# Tiny-RC-Serial.net
KiCad netlist of a schematic drawn in EAGLE
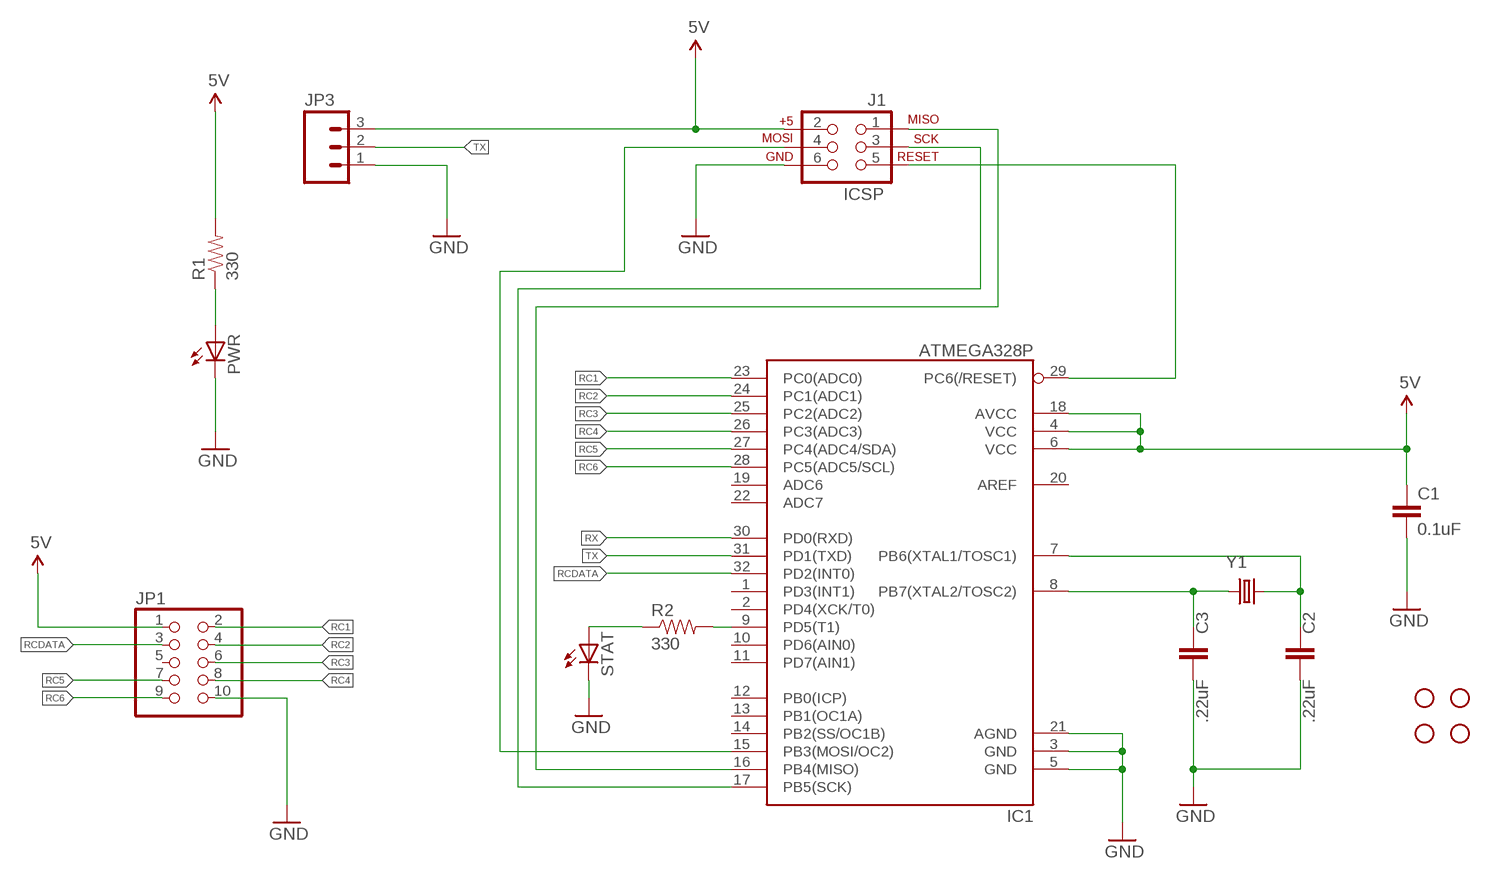
[diagram p0: schematic, sheet 1]

(export (version "E")
  (design (tool "Eeschema 10.0.6"))
  (components
    (comp (ref "C1")
      (value "0.1uF")
      (footprint "eagle-import:CAP-PTH-SMALL-KIT")
      (libsource (lib "eagle-import") (part "CAPKIT"))
    )
    (comp (ref "C2")
      (value ".22uF")
      (footprint "eagle-import:CAP-PTH-SMALL-KIT")
      (libsource (lib "eagle-import") (part "CAPKIT"))
    )
    (comp (ref "C3")
      (value ".22uF")
      (footprint "eagle-import:CAP-PTH-SMALL-KIT")
      (libsource (lib "eagle-import") (part "CAPKIT"))
    )
    (comp (ref "IC1")
      (value "ATMEGA328P")
      (footprint "eagle-import:TQFP32-08")
      (libsource (lib "eagle-import") (part "ATMEGA328_SMT"))
    )
    (comp (ref "J1")
      (value "ICSP")
      (footprint "eagle-import:2X3")
      (libsource (lib "eagle-import") (part "AVR_SPI_PRG_6PTH"))
    )
    (comp (ref "JP1")
      (value "PINHD-2X5")
      (footprint "eagle-import:2X05")
      (libsource (lib "eagle-import") (part "PINHD-2X5"))
    )
    (comp (ref "JP3")
      (value "M03PTH")
      (footprint "eagle-import:1X03")
      (libsource (lib "eagle-import") (part "M03PTH"))
    )
    (comp (ref "PWR")
      (value "LED1206")
      (footprint "eagle-import:LED-1206")
      (libsource (lib "eagle-import") (part "LED1206"))
    )
    (comp (ref "R1")
      (value "330")
      (footprint "eagle-import:1206")
      (libsource (lib "eagle-import") (part "RESISTOR1206"))
    )
    (comp (ref "R2")
      (value "330")
      (footprint "eagle-import:1206")
      (libsource (lib "eagle-import") (part "RESISTOR1206"))
    )
    (comp (ref "S1")
      (value "STAND-OFFTIGHT")
      (footprint "eagle-import:STAND-OFF-TIGHT")
      (libsource (lib "eagle-import") (part "STAND-OFFTIGHT"))
    )
    (comp (ref "S2")
      (value "STAND-OFFTIGHT")
      (footprint "eagle-import:STAND-OFF-TIGHT")
      (libsource (lib "eagle-import") (part "STAND-OFFTIGHT"))
    )
    (comp (ref "S3")
      (value "STAND-OFFTIGHT")
      (footprint "eagle-import:STAND-OFF-TIGHT")
      (libsource (lib "eagle-import") (part "STAND-OFFTIGHT"))
    )
    (comp (ref "S4")
      (value "STAND-OFFTIGHT")
      (footprint "eagle-import:STAND-OFF-TIGHT")
      (libsource (lib "eagle-import") (part "STAND-OFFTIGHT"))
    )
    (comp (ref "STAT")
      (value "LED1206")
      (footprint "eagle-import:LED-1206")
      (libsource (lib "eagle-import") (part "LED1206"))
    )
    (comp (ref "Y1")
      (value "20Mhz")
      (footprint "eagle-import:HC49US")
      (libsource (lib "eagle-import") (part "CRYSTALHC49US"))
    )
  )
  (nets
    (net (code "1") (name "5V") (class "Default")
      (node (ref "C1") (pin "1") (pinfunction "1_1") (pintype "passive"))
      (node (ref "IC1") (pin "18") (pinfunction "AVCC_18") (pintype "bidirectional"))
      (node (ref "IC1") (pin "4") (pinfunction "VCC_4") (pintype "bidirectional"))
      (node (ref "IC1") (pin "6") (pinfunction "VCC_6") (pintype "bidirectional"))
      (node (ref "J1") (pin "2") (pinfunction "2_2") (pintype "passive"))
      (node (ref "JP1") (pin "1") (pinfunction "1_1") (pintype "passive"))
      (node (ref "JP3") (pin "3") (pinfunction "3_3") (pintype "passive"))
      (node (ref "R1") (pin "2") (pinfunction "2_2") (pintype "passive"))
    )
    (net (code "2") (name "GND") (class "Default")
      (node (ref "C1") (pin "2") (pinfunction "2_2") (pintype "passive"))
      (node (ref "C2") (pin "2") (pinfunction "2_2") (pintype "passive"))
      (node (ref "C3") (pin "2") (pinfunction "2_2") (pintype "passive"))
      (node (ref "IC1") (pin "21") (pinfunction "AGND_21") (pintype "bidirectional"))
      (node (ref "IC1") (pin "3") (pinfunction "GND_3") (pintype "bidirectional"))
      (node (ref "IC1") (pin "5") (pinfunction "GND_5") (pintype "bidirectional"))
      (node (ref "J1") (pin "6") (pinfunction "6_6") (pintype "passive"))
      (node (ref "JP1") (pin "10") (pinfunction "10_10") (pintype "passive"))
      (node (ref "JP3") (pin "1") (pinfunction "1_1") (pintype "passive"))
      (node (ref "PWR") (pin "C") (pinfunction "C_C") (pintype "passive"))
      (node (ref "STAT") (pin "C") (pinfunction "C_C") (pintype "passive"))
    )
    (net (code "3") (name "Net-(IC1-PB3(MOSI{slash}OC2))") (class "Default")
      (node (ref "IC1") (pin "15") (pinfunction "PB3(MOSI/OC2)_15") (pintype "bidirectional"))
      (node (ref "J1") (pin "4") (pinfunction "4_4") (pintype "passive"))
    )
    (net (code "4") (name "Net-(IC1-PB4(MISO))") (class "Default")
      (node (ref "IC1") (pin "16") (pinfunction "PB4(MISO)_16") (pintype "bidirectional"))
      (node (ref "J1") (pin "1") (pinfunction "1_1") (pintype "passive"))
    )
    (net (code "5") (name "Net-(IC1-PB5(SCK))") (class "Default")
      (node (ref "IC1") (pin "17") (pinfunction "PB5(SCK)_17") (pintype "bidirectional"))
      (node (ref "J1") (pin "3") (pinfunction "3_3") (pintype "passive"))
    )
    (net (code "6") (name "Net-(IC1-PB6(XTAL1{slash}TOSC1))") (class "Default")
      (node (ref "C2") (pin "1") (pinfunction "1_1") (pintype "passive"))
      (node (ref "IC1") (pin "7") (pinfunction "PB6(XTAL1/TOSC1)_7") (pintype "bidirectional"))
      (node (ref "Y1") (pin "2") (pinfunction "2_2") (pintype "passive"))
    )
    (net (code "7") (name "Net-(IC1-PB7(XTAL2{slash}TOSC2))") (class "Default")
      (node (ref "C3") (pin "1") (pinfunction "1_1") (pintype "passive"))
      (node (ref "IC1") (pin "8") (pinfunction "PB7(XTAL2/TOSC2)_8") (pintype "bidirectional"))
      (node (ref "Y1") (pin "1") (pinfunction "1_1") (pintype "passive"))
    )
    (net (code "8") (name "Net-(IC1-PC6({slash}RESET))") (class "Default")
      (node (ref "IC1") (pin "29") (pinfunction "PC6(/RESET)_29") (pintype "bidirectional"))
      (node (ref "J1") (pin "5") (pinfunction "5_5") (pintype "passive"))
    )
    (net (code "9") (name "Net-(IC1-PD5(T1))") (class "Default")
      (node (ref "IC1") (pin "9") (pinfunction "PD5(T1)_9") (pintype "bidirectional"))
      (node (ref "R2") (pin "2") (pinfunction "2_2") (pintype "passive"))
    )
    (net (code "10") (name "Net-(PWR-PadA)") (class "Default")
      (node (ref "PWR") (pin "A") (pinfunction "A_A") (pintype "passive"))
      (node (ref "R1") (pin "1") (pinfunction "1_1") (pintype "passive"))
    )
    (net (code "11") (name "Net-(R2-Pad1)") (class "Default")
      (node (ref "R2") (pin "1") (pinfunction "1_1") (pintype "passive"))
      (node (ref "STAT") (pin "A") (pinfunction "A_A") (pintype "passive"))
    )
    (net (code "12") (name "RC1") (class "Default")
      (node (ref "IC1") (pin "23") (pinfunction "PC0(ADC0)_23") (pintype "bidirectional"))
      (node (ref "JP1") (pin "2") (pinfunction "2_2") (pintype "passive"))
    )
    (net (code "13") (name "RC2") (class "Default")
      (node (ref "IC1") (pin "24") (pinfunction "PC1(ADC1)_24") (pintype "bidirectional"))
      (node (ref "JP1") (pin "4") (pinfunction "4_4") (pintype "passive"))
    )
    (net (code "14") (name "RC3") (class "Default")
      (node (ref "IC1") (pin "25") (pinfunction "PC2(ADC2)_25") (pintype "bidirectional"))
      (node (ref "JP1") (pin "6") (pinfunction "6_6") (pintype "passive"))
    )
    (net (code "15") (name "RC4") (class "Default")
      (node (ref "IC1") (pin "26") (pinfunction "PC3(ADC3)_26") (pintype "bidirectional"))
      (node (ref "JP1") (pin "8") (pinfunction "8_8") (pintype "passive"))
    )
    (net (code "16") (name "RC5") (class "Default")
      (node (ref "IC1") (pin "27") (pinfunction "PC4(ADC4/SDA)_27") (pintype "bidirectional"))
      (node (ref "JP1") (pin "7") (pinfunction "7_7") (pintype "passive"))
    )
    (net (code "17") (name "RC6") (class "Default")
      (node (ref "IC1") (pin "28") (pinfunction "PC5(ADC5/SCL)_28") (pintype "bidirectional"))
      (node (ref "JP1") (pin "9") (pinfunction "9_9") (pintype "passive"))
    )
    (net (code "18") (name "RCDATA") (class "Default")
      (node (ref "IC1") (pin "32") (pinfunction "PD2(INT0)_32") (pintype "bidirectional"))
      (node (ref "JP1") (pin "3") (pinfunction "3_3") (pintype "passive"))
    )
    (net (code "19") (name "RX") (class "Default")
      (node (ref "IC1") (pin "30") (pinfunction "PD0(RXD)_30") (pintype "bidirectional"))
    )
    (net (code "20") (name "TX") (class "Default")
      (node (ref "IC1") (pin "31") (pinfunction "PD1(TXD)_31") (pintype "bidirectional"))
      (node (ref "JP3") (pin "2") (pinfunction "2_2") (pintype "passive"))
    )
    (net (code "21") (name "unconnected-(IC1-ADC6-Pad19)") (class "Default")
      (node (ref "IC1") (pin "19") (pinfunction "ADC6_19") (pintype "bidirectional"))
    )
    (net (code "22") (name "unconnected-(IC1-ADC7-Pad22)") (class "Default")
      (node (ref "IC1") (pin "22") (pinfunction "ADC7_22") (pintype "bidirectional"))
    )
    (net (code "23") (name "unconnected-(IC1-AREF-Pad20)") (class "Default")
      (node (ref "IC1") (pin "20") (pinfunction "AREF_20") (pintype "bidirectional"))
    )
    (net (code "24") (name "unconnected-(IC1-PB0(ICP)-Pad12)") (class "Default")
      (node (ref "IC1") (pin "12") (pinfunction "PB0(ICP)_12") (pintype "bidirectional"))
    )
    (net (code "25") (name "unconnected-(IC1-PB1(OC1A)-Pad13)") (class "Default")
      (node (ref "IC1") (pin "13") (pinfunction "PB1(OC1A)_13") (pintype "bidirectional"))
    )
    (net (code "26") (name "unconnected-(IC1-PB2(SS{slash}OC1B)-Pad14)") (class "Default")
      (node (ref "IC1") (pin "14") (pinfunction "PB2(SS/OC1B)_14") (pintype "bidirectional"))
    )
    (net (code "27") (name "unconnected-(IC1-PD3(INT1)-Pad1)") (class "Default")
      (node (ref "IC1") (pin "1") (pinfunction "PD3(INT1)_1") (pintype "bidirectional"))
    )
    (net (code "28") (name "unconnected-(IC1-PD4(XCK{slash}T0)-Pad2)") (class "Default")
      (node (ref "IC1") (pin "2") (pinfunction "PD4(XCK/T0)_2") (pintype "bidirectional"))
    )
    (net (code "29") (name "unconnected-(IC1-PD6(AIN0)-Pad10)") (class "Default")
      (node (ref "IC1") (pin "10") (pinfunction "PD6(AIN0)_10") (pintype "bidirectional"))
    )
    (net (code "30") (name "unconnected-(IC1-PD7(AIN1)-Pad11)") (class "Default")
      (node (ref "IC1") (pin "11") (pinfunction "PD7(AIN1)_11") (pintype "bidirectional"))
    )
    (net (code "31") (name "unconnected-(JP1-Pad5)") (class "Default")
      (node (ref "JP1") (pin "5") (pinfunction "5_5") (pintype "passive"))
    )
  )
)
